# Poloneiraol.net
KiCad netlist of a schematic drawn in EAGLE
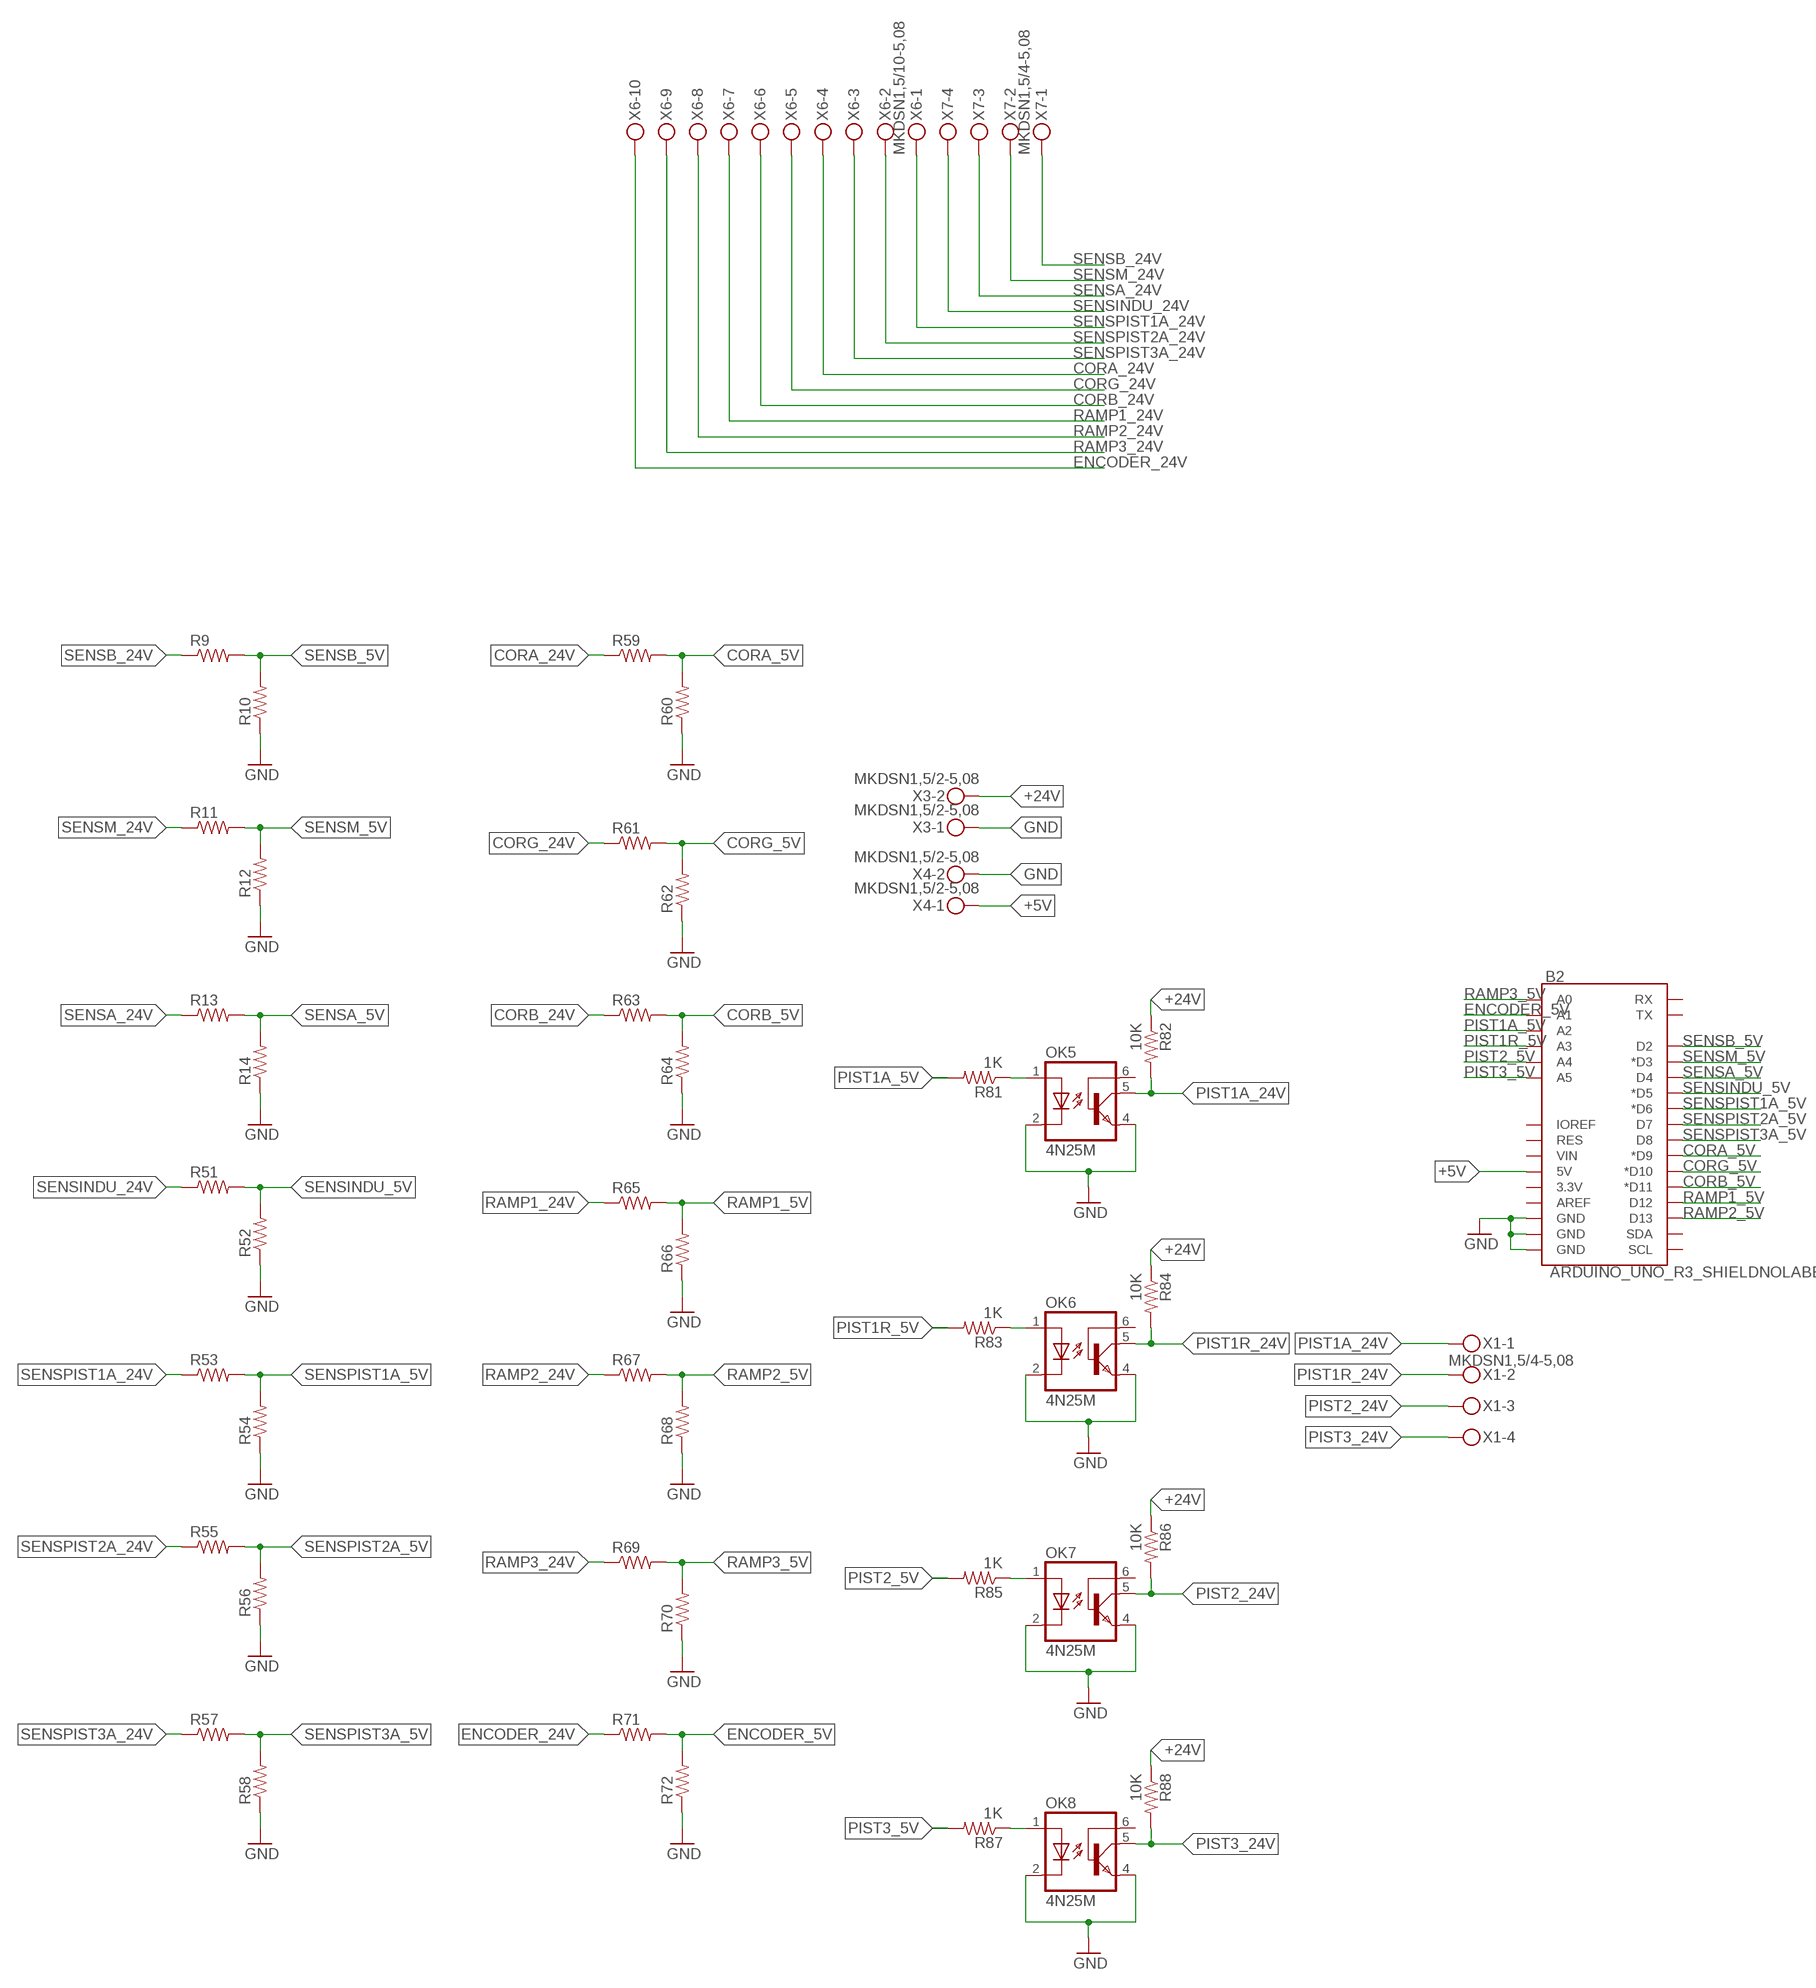
[diagram p0: schematic, sheet 1]

(export (version "E")
  (design (tool "Eeschema 10.0.6"))
  (components
    (comp (ref "B2")
      (value "ARDUINO_UNO_R3_SHIELDNOLABELS")
      (footprint "eagle-import:UNO_R3_SHIELD_NOLABELS")
      (libsource (lib "eagle-import") (part "ARDUINO_UNO_R3_SHIELDNOLABELS"))
    )
    (comp (ref "OK5")
      (value "4N25M")
      (footprint "eagle-import:DIL06")
      (fields (field (name "MPN") "4N25-M"))
      (libsource (lib "eagle-import") (part "4N?M25"))
    )
    (comp (ref "OK6")
      (value "4N25M")
      (footprint "eagle-import:DIL06")
      (fields (field (name "MPN") "4N25-M"))
      (libsource (lib "eagle-import") (part "4N?M25"))
    )
    (comp (ref "OK7")
      (value "4N25M")
      (footprint "eagle-import:DIL06")
      (fields (field (name "MPN") "4N25-M"))
      (libsource (lib "eagle-import") (part "4N?M25"))
    )
    (comp (ref "OK8")
      (value "4N25M")
      (footprint "eagle-import:DIL06")
      (fields (field (name "MPN") "4N25-M"))
      (libsource (lib "eagle-import") (part "4N?M25"))
    )
    (comp (ref "R9")
      (value "RESISTORAXIAL-0.3")
      (footprint "eagle-import:AXIAL-0.3")
      (libsource (lib "eagle-import") (part "RESISTORAXIAL-0.3"))
    )
    (comp (ref "R10")
      (value "RESISTORAXIAL-0.3")
      (footprint "eagle-import:AXIAL-0.3")
      (libsource (lib "eagle-import") (part "RESISTORAXIAL-0.3"))
    )
    (comp (ref "R11")
      (value "RESISTORAXIAL-0.3")
      (footprint "eagle-import:AXIAL-0.3")
      (libsource (lib "eagle-import") (part "RESISTORAXIAL-0.3"))
    )
    (comp (ref "R12")
      (value "RESISTORAXIAL-0.3")
      (footprint "eagle-import:AXIAL-0.3")
      (libsource (lib "eagle-import") (part "RESISTORAXIAL-0.3"))
    )
    (comp (ref "R13")
      (value "RESISTORAXIAL-0.3")
      (footprint "eagle-import:AXIAL-0.3")
      (libsource (lib "eagle-import") (part "RESISTORAXIAL-0.3"))
    )
    (comp (ref "R14")
      (value "RESISTORAXIAL-0.3")
      (footprint "eagle-import:AXIAL-0.3")
      (libsource (lib "eagle-import") (part "RESISTORAXIAL-0.3"))
    )
    (comp (ref "R51")
      (value "RESISTORAXIAL-0.3")
      (footprint "eagle-import:AXIAL-0.3")
      (libsource (lib "eagle-import") (part "RESISTORAXIAL-0.3"))
    )
    (comp (ref "R52")
      (value "RESISTORAXIAL-0.3")
      (footprint "eagle-import:AXIAL-0.3")
      (libsource (lib "eagle-import") (part "RESISTORAXIAL-0.3"))
    )
    (comp (ref "R53")
      (value "RESISTORAXIAL-0.3")
      (footprint "eagle-import:AXIAL-0.3")
      (libsource (lib "eagle-import") (part "RESISTORAXIAL-0.3"))
    )
    (comp (ref "R54")
      (value "RESISTORAXIAL-0.3")
      (footprint "eagle-import:AXIAL-0.3")
      (libsource (lib "eagle-import") (part "RESISTORAXIAL-0.3"))
    )
    (comp (ref "R55")
      (value "RESISTORAXIAL-0.3")
      (footprint "eagle-import:AXIAL-0.3")
      (libsource (lib "eagle-import") (part "RESISTORAXIAL-0.3"))
    )
    (comp (ref "R56")
      (value "RESISTORAXIAL-0.3")
      (footprint "eagle-import:AXIAL-0.3")
      (libsource (lib "eagle-import") (part "RESISTORAXIAL-0.3"))
    )
    (comp (ref "R57")
      (value "RESISTORAXIAL-0.3")
      (footprint "eagle-import:AXIAL-0.3")
      (libsource (lib "eagle-import") (part "RESISTORAXIAL-0.3"))
    )
    (comp (ref "R58")
      (value "RESISTORAXIAL-0.3")
      (footprint "eagle-import:AXIAL-0.3")
      (libsource (lib "eagle-import") (part "RESISTORAXIAL-0.3"))
    )
    (comp (ref "R59")
      (value "RESISTORAXIAL-0.3")
      (footprint "eagle-import:AXIAL-0.3")
      (libsource (lib "eagle-import") (part "RESISTORAXIAL-0.3"))
    )
    (comp (ref "R60")
      (value "RESISTORAXIAL-0.3")
      (footprint "eagle-import:AXIAL-0.3")
      (libsource (lib "eagle-import") (part "RESISTORAXIAL-0.3"))
    )
    (comp (ref "R61")
      (value "RESISTORAXIAL-0.3")
      (footprint "eagle-import:AXIAL-0.3")
      (libsource (lib "eagle-import") (part "RESISTORAXIAL-0.3"))
    )
    (comp (ref "R62")
      (value "RESISTORAXIAL-0.3")
      (footprint "eagle-import:AXIAL-0.3")
      (libsource (lib "eagle-import") (part "RESISTORAXIAL-0.3"))
    )
    (comp (ref "R63")
      (value "RESISTORAXIAL-0.3")
      (footprint "eagle-import:AXIAL-0.3")
      (libsource (lib "eagle-import") (part "RESISTORAXIAL-0.3"))
    )
    (comp (ref "R64")
      (value "RESISTORAXIAL-0.3")
      (footprint "eagle-import:AXIAL-0.3")
      (libsource (lib "eagle-import") (part "RESISTORAXIAL-0.3"))
    )
    (comp (ref "R65")
      (value "RESISTORAXIAL-0.3")
      (footprint "eagle-import:AXIAL-0.3")
      (libsource (lib "eagle-import") (part "RESISTORAXIAL-0.3"))
    )
    (comp (ref "R66")
      (value "RESISTORAXIAL-0.3")
      (footprint "eagle-import:AXIAL-0.3")
      (libsource (lib "eagle-import") (part "RESISTORAXIAL-0.3"))
    )
    (comp (ref "R67")
      (value "RESISTORAXIAL-0.3")
      (footprint "eagle-import:AXIAL-0.3")
      (libsource (lib "eagle-import") (part "RESISTORAXIAL-0.3"))
    )
    (comp (ref "R68")
      (value "RESISTORAXIAL-0.3")
      (footprint "eagle-import:AXIAL-0.3")
      (libsource (lib "eagle-import") (part "RESISTORAXIAL-0.3"))
    )
    (comp (ref "R69")
      (value "RESISTORAXIAL-0.3")
      (footprint "eagle-import:AXIAL-0.3")
      (libsource (lib "eagle-import") (part "RESISTORAXIAL-0.3"))
    )
    (comp (ref "R70")
      (value "RESISTORAXIAL-0.3")
      (footprint "eagle-import:AXIAL-0.3")
      (libsource (lib "eagle-import") (part "RESISTORAXIAL-0.3"))
    )
    (comp (ref "R71")
      (value "RESISTORAXIAL-0.3")
      (footprint "eagle-import:AXIAL-0.3")
      (libsource (lib "eagle-import") (part "RESISTORAXIAL-0.3"))
    )
    (comp (ref "R72")
      (value "RESISTORAXIAL-0.3")
      (footprint "eagle-import:AXIAL-0.3")
      (libsource (lib "eagle-import") (part "RESISTORAXIAL-0.3"))
    )
    (comp (ref "R81")
      (value "1K")
      (footprint "eagle-import:AXIAL-0.3EZ")
      (libsource (lib "eagle-import") (part "1KOHM-1/4W-1%(PTH)HORIZ-KIT"))
    )
    (comp (ref "R82")
      (value "10K")
      (footprint "eagle-import:AXIAL-0.3EZ")
      (libsource (lib "eagle-import") (part "1KOHM-1/4W-1%(PTH)HORIZ-KIT"))
    )
    (comp (ref "R83")
      (value "1K")
      (footprint "eagle-import:AXIAL-0.3EZ")
      (libsource (lib "eagle-import") (part "1KOHM-1/4W-1%(PTH)HORIZ-KIT"))
    )
    (comp (ref "R84")
      (value "10K")
      (footprint "eagle-import:AXIAL-0.3EZ")
      (libsource (lib "eagle-import") (part "1KOHM-1/4W-1%(PTH)HORIZ-KIT"))
    )
    (comp (ref "R85")
      (value "1K")
      (footprint "eagle-import:AXIAL-0.3EZ")
      (libsource (lib "eagle-import") (part "1KOHM-1/4W-1%(PTH)HORIZ-KIT"))
    )
    (comp (ref "R86")
      (value "10K")
      (footprint "eagle-import:AXIAL-0.3")
      (libsource (lib "eagle-import") (part "RESISTORAXIAL-0.3"))
    )
    (comp (ref "R87")
      (value "1K")
      (footprint "eagle-import:AXIAL-0.3EZ")
      (libsource (lib "eagle-import") (part "1KOHM-1/4W-1%(PTH)HORIZ-KIT"))
    )
    (comp (ref "R88")
      (value "10K")
      (footprint "eagle-import:AXIAL-0.3EZ")
      (libsource (lib "eagle-import") (part "1KOHM-1/4W-1%(PTH)HORIZ-KIT"))
    )
    (comp (ref "X1")
      (value "MKDSN1,5/4-5,08")
      (footprint "eagle-import:MKDSN1,5_4-5,08")
      (libsource (lib "eagle-import") (part "MKDSN1,5/4-5,08"))
    )
    (comp (ref "X3")
      (value "MKDSN1,5/2-5,08")
      (footprint "eagle-import:MKDSN1,5_2-5,08")
      (libsource (lib "eagle-import") (part "MKDSN1,5/2-5,08"))
    )
    (comp (ref "X4")
      (value "MKDSN1,5/2-5,08")
      (footprint "eagle-import:MKDSN1,5_2-5,08")
      (libsource (lib "eagle-import") (part "MKDSN1,5/2-5,08"))
    )
    (comp (ref "X6")
      (value "MKDSN1,5/10-5,08")
      (footprint "eagle-import:MKDSN1,5_10-5,08")
      (libsource (lib "eagle-import") (part "MKDSN1,5/10-5,08"))
    )
    (comp (ref "X7")
      (value "MKDSN1,5/4-5,08")
      (footprint "eagle-import:MKDSN1,5_4-5,08")
      (libsource (lib "eagle-import") (part "MKDSN1,5/4-5,08"))
    )
  )
  (nets
    (net (code "1") (name "+5V") (class "Default")
      (node (ref "B2") (pin "5V") (pinfunction "5V_5V") (pintype "bidirectional"))
      (node (ref "X4") (pin "1") (pinfunction "KL_1") (pintype "passive"))
    )
    (net (code "2") (name "+24V") (class "Default")
      (node (ref "R82") (pin "P$1") (pinfunction "1_P$1") (pintype "passive"))
      (node (ref "R84") (pin "P$1") (pinfunction "1_P$1") (pintype "passive"))
      (node (ref "R86") (pin "P$1") (pinfunction "1_P$1") (pintype "passive"))
      (node (ref "R88") (pin "P$1") (pinfunction "1_P$1") (pintype "passive"))
      (node (ref "X3") (pin "2") (pinfunction "KL_2") (pintype "passive"))
    )
    (net (code "3") (name "CORA_5V") (class "Default")
      (node (ref "B2") (pin "D9") (pinfunction "*D9_D9") (pintype "bidirectional"))
      (node (ref "R59") (pin "P$2") (pinfunction "2_P$2") (pintype "passive"))
      (node (ref "R60") (pin "P$2") (pinfunction "2_P$2") (pintype "passive"))
    )
    (net (code "4") (name "CORA_24V") (class "Default")
      (node (ref "R59") (pin "P$1") (pinfunction "1_P$1") (pintype "passive"))
      (node (ref "X6") (pin "4") (pinfunction "KL_4") (pintype "passive"))
    )
    (net (code "5") (name "CORB_5V") (class "Default")
      (node (ref "B2") (pin "D11") (pinfunction "*D11_D11") (pintype "bidirectional"))
      (node (ref "R63") (pin "P$2") (pinfunction "2_P$2") (pintype "passive"))
      (node (ref "R64") (pin "P$2") (pinfunction "2_P$2") (pintype "passive"))
    )
    (net (code "6") (name "CORB_24V") (class "Default")
      (node (ref "R63") (pin "P$1") (pinfunction "1_P$1") (pintype "passive"))
      (node (ref "X6") (pin "6") (pinfunction "KL_6") (pintype "passive"))
    )
    (net (code "7") (name "CORG_5V") (class "Default")
      (node (ref "B2") (pin "D10") (pinfunction "*D10_D10") (pintype "bidirectional"))
      (node (ref "R61") (pin "P$2") (pinfunction "2_P$2") (pintype "passive"))
      (node (ref "R62") (pin "P$2") (pinfunction "2_P$2") (pintype "passive"))
    )
    (net (code "8") (name "CORG_24V") (class "Default")
      (node (ref "R61") (pin "P$1") (pinfunction "1_P$1") (pintype "passive"))
      (node (ref "X6") (pin "5") (pinfunction "KL_5") (pintype "passive"))
    )
    (net (code "9") (name "ENCODER_5V") (class "Default")
      (node (ref "B2") (pin "A1") (pinfunction "A1_A1") (pintype "bidirectional"))
      (node (ref "R71") (pin "P$2") (pinfunction "2_P$2") (pintype "passive"))
      (node (ref "R72") (pin "P$2") (pinfunction "2_P$2") (pintype "passive"))
    )
    (net (code "10") (name "ENCODER_24V") (class "Default")
      (node (ref "R71") (pin "P$1") (pinfunction "1_P$1") (pintype "passive"))
      (node (ref "X6") (pin "10") (pinfunction "KL_10") (pintype "passive"))
    )
    (net (code "11") (name "GND") (class "Default")
      (node (ref "B2") (pin "GND@0") (pinfunction "GND_GND@0") (pintype "bidirectional"))
      (node (ref "B2") (pin "GND@1") (pinfunction "GND_GND@1") (pintype "bidirectional"))
      (node (ref "B2") (pin "GND@2") (pinfunction "GND_GND@2") (pintype "bidirectional"))
      (node (ref "OK5") (pin "2") (pinfunction "C_2") (pintype "passive"))
      (node (ref "OK5") (pin "4") (pinfunction "EMI_4") (pintype "passive"))
      (node (ref "OK6") (pin "2") (pinfunction "C_2") (pintype "passive"))
      (node (ref "OK6") (pin "4") (pinfunction "EMI_4") (pintype "passive"))
      (node (ref "OK7") (pin "2") (pinfunction "C_2") (pintype "passive"))
      (node (ref "OK7") (pin "4") (pinfunction "EMI_4") (pintype "passive"))
      (node (ref "OK8") (pin "2") (pinfunction "C_2") (pintype "passive"))
      (node (ref "OK8") (pin "4") (pinfunction "EMI_4") (pintype "passive"))
      (node (ref "R10") (pin "P$1") (pinfunction "1_P$1") (pintype "passive"))
      (node (ref "R12") (pin "P$1") (pinfunction "1_P$1") (pintype "passive"))
      (node (ref "R14") (pin "P$1") (pinfunction "1_P$1") (pintype "passive"))
      (node (ref "R52") (pin "P$1") (pinfunction "1_P$1") (pintype "passive"))
      (node (ref "R54") (pin "P$1") (pinfunction "1_P$1") (pintype "passive"))
      (node (ref "R56") (pin "P$1") (pinfunction "1_P$1") (pintype "passive"))
      (node (ref "R58") (pin "P$1") (pinfunction "1_P$1") (pintype "passive"))
      (node (ref "R60") (pin "P$1") (pinfunction "1_P$1") (pintype "passive"))
      (node (ref "R62") (pin "P$1") (pinfunction "1_P$1") (pintype "passive"))
      (node (ref "R64") (pin "P$1") (pinfunction "1_P$1") (pintype "passive"))
      (node (ref "R66") (pin "P$1") (pinfunction "1_P$1") (pintype "passive"))
      (node (ref "R68") (pin "P$1") (pinfunction "1_P$1") (pintype "passive"))
      (node (ref "R70") (pin "P$1") (pinfunction "1_P$1") (pintype "passive"))
      (node (ref "R72") (pin "P$1") (pinfunction "1_P$1") (pintype "passive"))
      (node (ref "X3") (pin "1") (pinfunction "KL_1") (pintype "passive"))
      (node (ref "X4") (pin "2") (pinfunction "KL_2") (pintype "passive"))
    )
    (net (code "12") (name "Net-(OK5-A)") (class "Default")
      (node (ref "OK5") (pin "1") (pinfunction "A_1") (pintype "passive"))
      (node (ref "R81") (pin "P$1") (pinfunction "1_P$1") (pintype "passive"))
    )
    (net (code "13") (name "Net-(OK6-A)") (class "Default")
      (node (ref "OK6") (pin "1") (pinfunction "A_1") (pintype "passive"))
      (node (ref "R83") (pin "P$1") (pinfunction "1_P$1") (pintype "passive"))
    )
    (net (code "14") (name "Net-(OK7-A)") (class "Default")
      (node (ref "OK7") (pin "1") (pinfunction "A_1") (pintype "passive"))
      (node (ref "R85") (pin "P$1") (pinfunction "1_P$1") (pintype "passive"))
    )
    (net (code "15") (name "Net-(OK8-A)") (class "Default")
      (node (ref "OK8") (pin "1") (pinfunction "A_1") (pintype "passive"))
      (node (ref "R87") (pin "P$1") (pinfunction "1_P$1") (pintype "passive"))
    )
    (net (code "16") (name "PIST1A_5V") (class "Default")
      (node (ref "B2") (pin "A2") (pinfunction "A2_A2") (pintype "bidirectional"))
      (node (ref "R81") (pin "P$2") (pinfunction "2_P$2") (pintype "passive"))
    )
    (net (code "17") (name "PIST1A_24V") (class "Default")
      (node (ref "OK5") (pin "5") (pinfunction "COL_5") (pintype "passive"))
      (node (ref "R82") (pin "P$2") (pinfunction "2_P$2") (pintype "passive"))
      (node (ref "X1") (pin "1") (pinfunction "KL_1") (pintype "passive"))
    )
    (net (code "18") (name "PIST1R_5V") (class "Default")
      (node (ref "B2") (pin "A3") (pinfunction "A3_A3") (pintype "bidirectional"))
      (node (ref "R83") (pin "P$2") (pinfunction "2_P$2") (pintype "passive"))
    )
    (net (code "19") (name "PIST1R_24V") (class "Default")
      (node (ref "OK6") (pin "5") (pinfunction "COL_5") (pintype "passive"))
      (node (ref "R84") (pin "P$2") (pinfunction "2_P$2") (pintype "passive"))
      (node (ref "X1") (pin "2") (pinfunction "KL_2") (pintype "passive"))
    )
    (net (code "20") (name "PIST2_5V") (class "Default")
      (node (ref "B2") (pin "A4") (pinfunction "A4_A4") (pintype "bidirectional"))
      (node (ref "R85") (pin "P$2") (pinfunction "2_P$2") (pintype "passive"))
    )
    (net (code "21") (name "PIST2_24V") (class "Default")
      (node (ref "OK7") (pin "5") (pinfunction "COL_5") (pintype "passive"))
      (node (ref "R86") (pin "P$2") (pinfunction "2_P$2") (pintype "passive"))
      (node (ref "X1") (pin "3") (pinfunction "KL_3") (pintype "passive"))
    )
    (net (code "22") (name "PIST3_5V") (class "Default")
      (node (ref "B2") (pin "A5") (pinfunction "A5_A5") (pintype "bidirectional"))
      (node (ref "R87") (pin "P$2") (pinfunction "2_P$2") (pintype "passive"))
    )
    (net (code "23") (name "PIST3_24V") (class "Default")
      (node (ref "OK8") (pin "5") (pinfunction "COL_5") (pintype "passive"))
      (node (ref "R88") (pin "P$2") (pinfunction "2_P$2") (pintype "passive"))
      (node (ref "X1") (pin "4") (pinfunction "KL_4") (pintype "passive"))
    )
    (net (code "24") (name "RAMP1_5V") (class "Default")
      (node (ref "B2") (pin "D12") (pinfunction "D12_D12") (pintype "bidirectional"))
      (node (ref "R65") (pin "P$2") (pinfunction "2_P$2") (pintype "passive"))
      (node (ref "R66") (pin "P$2") (pinfunction "2_P$2") (pintype "passive"))
    )
    (net (code "25") (name "RAMP1_24V") (class "Default")
      (node (ref "R65") (pin "P$1") (pinfunction "1_P$1") (pintype "passive"))
      (node (ref "X6") (pin "7") (pinfunction "KL_7") (pintype "passive"))
    )
    (net (code "26") (name "RAMP2_5V") (class "Default")
      (node (ref "B2") (pin "D13") (pinfunction "D13_D13") (pintype "bidirectional"))
      (node (ref "R67") (pin "P$2") (pinfunction "2_P$2") (pintype "passive"))
      (node (ref "R68") (pin "P$2") (pinfunction "2_P$2") (pintype "passive"))
    )
    (net (code "27") (name "RAMP2_24V") (class "Default")
      (node (ref "R67") (pin "P$1") (pinfunction "1_P$1") (pintype "passive"))
      (node (ref "X6") (pin "8") (pinfunction "KL_8") (pintype "passive"))
    )
    (net (code "28") (name "RAMP3_5V") (class "Default")
      (node (ref "B2") (pin "A0") (pinfunction "A0_A0") (pintype "bidirectional"))
      (node (ref "R69") (pin "P$2") (pinfunction "2_P$2") (pintype "passive"))
      (node (ref "R70") (pin "P$2") (pinfunction "2_P$2") (pintype "passive"))
    )
    (net (code "29") (name "RAMP3_24V") (class "Default")
      (node (ref "R69") (pin "P$1") (pinfunction "1_P$1") (pintype "passive"))
      (node (ref "X6") (pin "9") (pinfunction "KL_9") (pintype "passive"))
    )
    (net (code "30") (name "SENSA_5V") (class "Default")
      (node (ref "B2") (pin "D4") (pinfunction "D4_D4") (pintype "bidirectional"))
      (node (ref "R13") (pin "P$2") (pinfunction "2_P$2") (pintype "passive"))
      (node (ref "R14") (pin "P$2") (pinfunction "2_P$2") (pintype "passive"))
    )
    (net (code "31") (name "SENSA_24V") (class "Default")
      (node (ref "R13") (pin "P$1") (pinfunction "1_P$1") (pintype "passive"))
      (node (ref "X7") (pin "3") (pinfunction "KL_3") (pintype "passive"))
    )
    (net (code "32") (name "SENSB_5V") (class "Default")
      (node (ref "B2") (pin "D2") (pinfunction "D2_D2") (pintype "bidirectional"))
      (node (ref "R10") (pin "P$2") (pinfunction "2_P$2") (pintype "passive"))
      (node (ref "R9") (pin "P$2") (pinfunction "2_P$2") (pintype "passive"))
    )
    (net (code "33") (name "SENSB_24V") (class "Default")
      (node (ref "R9") (pin "P$1") (pinfunction "1_P$1") (pintype "passive"))
      (node (ref "X7") (pin "1") (pinfunction "KL_1") (pintype "passive"))
    )
    (net (code "34") (name "SENSINDU_5V") (class "Default")
      (node (ref "B2") (pin "D5") (pinfunction "*D5_D5") (pintype "bidirectional"))
      (node (ref "R51") (pin "P$2") (pinfunction "2_P$2") (pintype "passive"))
      (node (ref "R52") (pin "P$2") (pinfunction "2_P$2") (pintype "passive"))
    )
    (net (code "35") (name "SENSINDU_24V") (class "Default")
      (node (ref "R51") (pin "P$1") (pinfunction "1_P$1") (pintype "passive"))
      (node (ref "X7") (pin "4") (pinfunction "KL_4") (pintype "passive"))
    )
    (net (code "36") (name "SENSM_5V") (class "Default")
      (node (ref "B2") (pin "D3") (pinfunction "*D3_D3") (pintype "bidirectional"))
      (node (ref "R11") (pin "P$2") (pinfunction "2_P$2") (pintype "passive"))
      (node (ref "R12") (pin "P$2") (pinfunction "2_P$2") (pintype "passive"))
    )
    (net (code "37") (name "SENSM_24V") (class "Default")
      (node (ref "R11") (pin "P$1") (pinfunction "1_P$1") (pintype "passive"))
      (node (ref "X7") (pin "2") (pinfunction "KL_2") (pintype "passive"))
    )
    (net (code "38") (name "SENSPIST1A_5V") (class "Default")
      (node (ref "B2") (pin "D6") (pinfunction "*D6_D6") (pintype "bidirectional"))
      (node (ref "R53") (pin "P$2") (pinfunction "2_P$2") (pintype "passive"))
      (node (ref "R54") (pin "P$2") (pinfunction "2_P$2") (pintype "passive"))
    )
    (net (code "39") (name "SENSPIST1A_24V") (class "Default")
      (node (ref "R53") (pin "P$1") (pinfunction "1_P$1") (pintype "passive"))
      (node (ref "X6") (pin "1") (pinfunction "KL_1") (pintype "passive"))
    )
    (net (code "40") (name "SENSPIST2A_5V") (class "Default")
      (node (ref "B2") (pin "D7") (pinfunction "D7_D7") (pintype "bidirectional"))
      (node (ref "R55") (pin "P$2") (pinfunction "2_P$2") (pintype "passive"))
      (node (ref "R56") (pin "P$2") (pinfunction "2_P$2") (pintype "passive"))
    )
    (net (code "41") (name "SENSPIST2A_24V") (class "Default")
      (node (ref "R55") (pin "P$1") (pinfunction "1_P$1") (pintype "passive"))
      (node (ref "X6") (pin "2") (pinfunction "KL_2") (pintype "passive"))
    )
    (net (code "42") (name "SENSPIST3A_5V") (class "Default")
      (node (ref "B2") (pin "D8") (pinfunction "D8_D8") (pintype "bidirectional"))
      (node (ref "R57") (pin "P$2") (pinfunction "2_P$2") (pintype "passive"))
      (node (ref "R58") (pin "P$2") (pinfunction "2_P$2") (pintype "passive"))
    )
    (net (code "43") (name "SENSPIST3A_24V") (class "Default")
      (node (ref "R57") (pin "P$1") (pinfunction "1_P$1") (pintype "passive"))
      (node (ref "X6") (pin "3") (pinfunction "KL_3") (pintype "passive"))
    )
    (net (code "44") (name "unconnected-(B2-Pad3.3V)") (class "Default")
      (node (ref "B2") (pin "3.3V") (pinfunction "3.3V_3.3V") (pintype "bidirectional"))
    )
    (net (code "45") (name "unconnected-(B2-PadAREF)") (class "Default")
      (node (ref "B2") (pin "AREF") (pinfunction "AREF_AREF") (pintype "bidirectional"))
    )
    (net (code "46") (name "unconnected-(B2-PadIOREF)") (class "Default")
      (node (ref "B2") (pin "IOREF") (pinfunction "IOREF_IOREF") (pintype "bidirectional"))
    )
    (net (code "47") (name "unconnected-(B2-PadRES)") (class "Default")
      (node (ref "B2") (pin "RES") (pinfunction "RES_RES") (pintype "bidirectional"))
    )
    (net (code "48") (name "unconnected-(B2-PadRX)") (class "Default")
      (node (ref "B2") (pin "RX") (pinfunction "RX_RX") (pintype "bidirectional"))
    )
    (net (code "49") (name "unconnected-(B2-PadSCL)") (class "Default")
      (node (ref "B2") (pin "SCL") (pinfunction "SCL_SCL") (pintype "bidirectional"))
    )
    (net (code "50") (name "unconnected-(B2-PadSDA)") (class "Default")
      (node (ref "B2") (pin "SDA") (pinfunction "SDA_SDA") (pintype "bidirectional"))
    )
    (net (code "51") (name "unconnected-(B2-PadTX)") (class "Default")
      (node (ref "B2") (pin "TX") (pinfunction "TX_TX") (pintype "bidirectional"))
    )
    (net (code "52") (name "unconnected-(B2-PadVIN)") (class "Default")
      (node (ref "B2") (pin "VIN") (pinfunction "VIN_VIN") (pintype "bidirectional"))
    )
    (net (code "53") (name "unconnected-(OK5-BAS-Pad6)") (class "Default")
      (node (ref "OK5") (pin "6") (pinfunction "BAS_6") (pintype "passive"))
    )
    (net (code "54") (name "unconnected-(OK6-BAS-Pad6)") (class "Default")
      (node (ref "OK6") (pin "6") (pinfunction "BAS_6") (pintype "passive"))
    )
    (net (code "55") (name "unconnected-(OK7-BAS-Pad6)") (class "Default")
      (node (ref "OK7") (pin "6") (pinfunction "BAS_6") (pintype "passive"))
    )
    (net (code "56") (name "unconnected-(OK8-BAS-Pad6)") (class "Default")
      (node (ref "OK8") (pin "6") (pinfunction "BAS_6") (pintype "passive"))
    )
  )
)
